# OBS-buttons-buttons.net
KiCad netlist of a schematic drawn in EAGLE
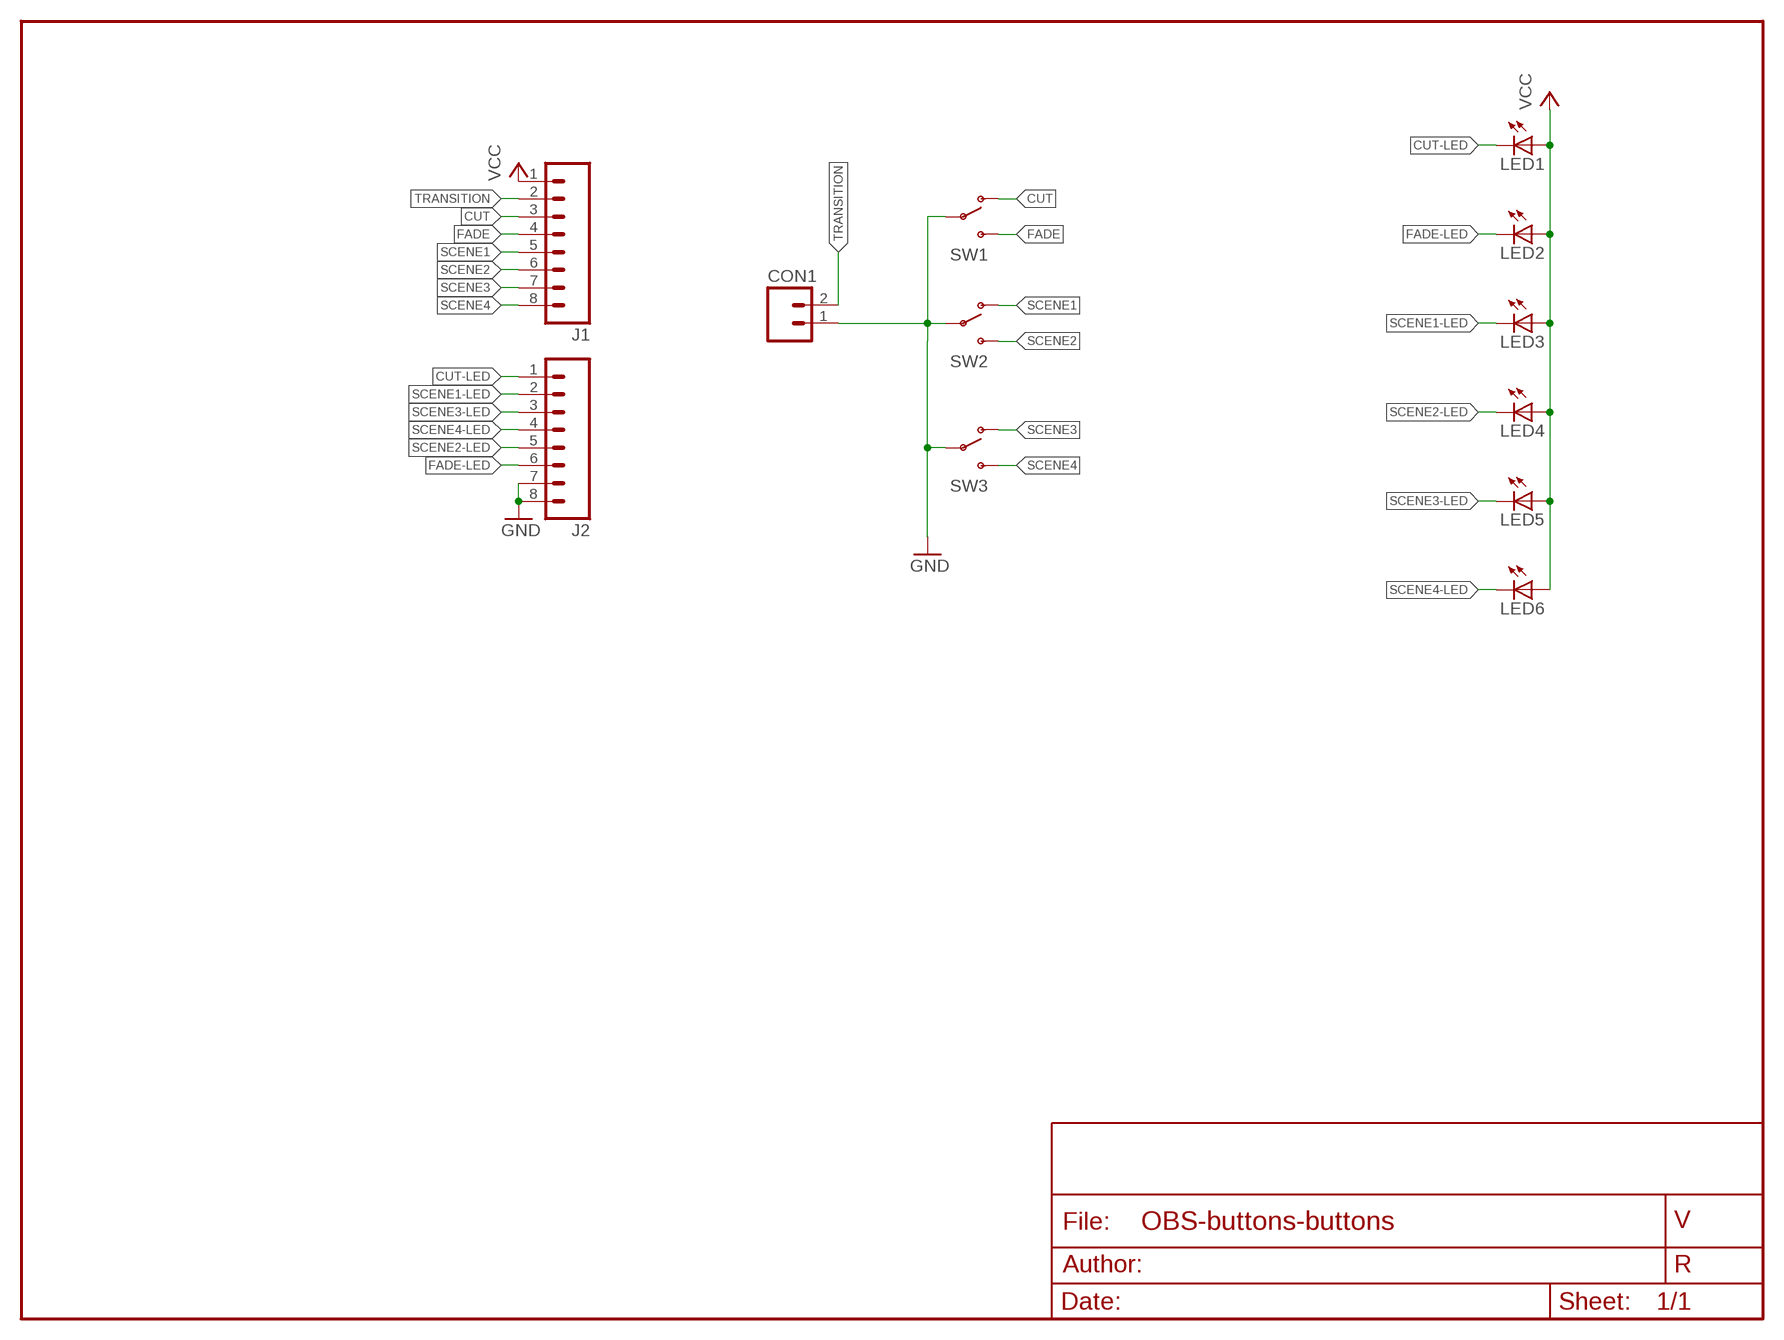
[diagram p0: schematic, sheet 1]

(export (version "E")
  (design (tool "Eeschema 10.0.6"))
  (components
    (comp (ref "CON1")
      (value "CONNECTOR-M02508-LOCK")
      (footprint "eagle-import:MSTB2")
      (libsource (lib "eagle-import") (part "CONNECTOR-M02508-LOCK"))
    )
    (comp (ref "J1")
      (value "CONNECTOR-M08LOCK")
      (footprint "eagle-import:1X08_LOCK")
      (libsource (lib "eagle-import") (part "CONNECTOR-M08LOCK"))
    )
    (comp (ref "J2")
      (value "CONNECTOR-M08LOCK")
      (footprint "eagle-import:1X08_LOCK")
      (libsource (lib "eagle-import") (part "CONNECTOR-M08LOCK"))
    )
    (comp (ref "LED1")
      (value "LEDLED5MM")
      (footprint "eagle-import:LED5MM")
      (libsource (lib "eagle-import") (part "LEDLED5MM"))
    )
    (comp (ref "LED2")
      (value "LEDLED5MM")
      (footprint "eagle-import:LED5MM")
      (libsource (lib "eagle-import") (part "LEDLED5MM"))
    )
    (comp (ref "LED3")
      (value "LEDLED5MM")
      (footprint "eagle-import:LED5MM")
      (libsource (lib "eagle-import") (part "LEDLED5MM"))
    )
    (comp (ref "LED4")
      (value "LEDLED5MM")
      (footprint "eagle-import:LED5MM")
      (libsource (lib "eagle-import") (part "LEDLED5MM"))
    )
    (comp (ref "LED5")
      (value "LEDLED5MM")
      (footprint "eagle-import:LED5MM")
      (libsource (lib "eagle-import") (part "LEDLED5MM"))
    )
    (comp (ref "LED6")
      (value "LEDLED5MM")
      (footprint "eagle-import:LED5MM")
      (libsource (lib "eagle-import") (part "LEDLED5MM"))
    )
    (comp (ref "SW1")
      (value "SWITCH-SPSTPTH-508")
      (footprint "eagle-import:SWITCH-SPDT-508")
      (libsource (lib "eagle-import") (part "SWITCH-SPSTPTH-508"))
    )
    (comp (ref "SW2")
      (value "SWITCH-SPSTPTH-508")
      (footprint "eagle-import:SWITCH-SPDT-508")
      (libsource (lib "eagle-import") (part "SWITCH-SPSTPTH-508"))
    )
    (comp (ref "SW3")
      (value "SWITCH-SPSTPTH-508")
      (footprint "eagle-import:SWITCH-SPDT-508")
      (libsource (lib "eagle-import") (part "SWITCH-SPSTPTH-508"))
    )
  )
  (nets
    (net (code "1") (name "CUT") (class "Default")
      (node (ref "J1") (pin "3") (pinfunction "3_3") (pintype "passive"))
      (node (ref "SW1") (pin "1") (pinfunction "O_1") (pintype "passive"))
    )
    (net (code "2") (name "CUT-LED") (class "Default")
      (node (ref "J2") (pin "1") (pinfunction "1_1") (pintype "passive"))
      (node (ref "LED1") (pin "K") (pinfunction "C_K") (pintype "passive"))
    )
    (net (code "3") (name "FADE") (class "Default")
      (node (ref "J1") (pin "4") (pinfunction "4_4") (pintype "passive"))
      (node (ref "SW1") (pin "3") (pinfunction "S_3") (pintype "passive"))
    )
    (net (code "4") (name "FADE-LED") (class "Default")
      (node (ref "J2") (pin "6") (pinfunction "6_6") (pintype "passive"))
      (node (ref "LED2") (pin "K") (pinfunction "C_K") (pintype "passive"))
    )
    (net (code "5") (name "GND") (class "Default")
      (node (ref "CON1") (pin "1") (pinfunction "A_1") (pintype "passive"))
      (node (ref "J2") (pin "7") (pinfunction "7_7") (pintype "passive"))
      (node (ref "J2") (pin "8") (pinfunction "8_8") (pintype "passive"))
      (node (ref "SW1") (pin "2") (pinfunction "P_2") (pintype "passive"))
      (node (ref "SW2") (pin "2") (pinfunction "P_2") (pintype "passive"))
      (node (ref "SW3") (pin "2") (pinfunction "P_2") (pintype "passive"))
    )
    (net (code "6") (name "SCENE1") (class "Default")
      (node (ref "J1") (pin "5") (pinfunction "5_5") (pintype "passive"))
      (node (ref "SW2") (pin "1") (pinfunction "O_1") (pintype "passive"))
    )
    (net (code "7") (name "SCENE1-LED") (class "Default")
      (node (ref "J2") (pin "2") (pinfunction "2_2") (pintype "passive"))
      (node (ref "LED3") (pin "K") (pinfunction "C_K") (pintype "passive"))
    )
    (net (code "8") (name "SCENE2") (class "Default")
      (node (ref "J1") (pin "6") (pinfunction "6_6") (pintype "passive"))
      (node (ref "SW2") (pin "3") (pinfunction "S_3") (pintype "passive"))
    )
    (net (code "9") (name "SCENE2-LED") (class "Default")
      (node (ref "J2") (pin "5") (pinfunction "5_5") (pintype "passive"))
      (node (ref "LED4") (pin "K") (pinfunction "C_K") (pintype "passive"))
    )
    (net (code "10") (name "SCENE3") (class "Default")
      (node (ref "J1") (pin "7") (pinfunction "7_7") (pintype "passive"))
      (node (ref "SW3") (pin "1") (pinfunction "O_1") (pintype "passive"))
    )
    (net (code "11") (name "SCENE3-LED") (class "Default")
      (node (ref "J2") (pin "3") (pinfunction "3_3") (pintype "passive"))
      (node (ref "LED5") (pin "K") (pinfunction "C_K") (pintype "passive"))
    )
    (net (code "12") (name "SCENE4") (class "Default")
      (node (ref "J1") (pin "8") (pinfunction "8_8") (pintype "passive"))
      (node (ref "SW3") (pin "3") (pinfunction "S_3") (pintype "passive"))
    )
    (net (code "13") (name "SCENE4-LED") (class "Default")
      (node (ref "J2") (pin "4") (pinfunction "4_4") (pintype "passive"))
      (node (ref "LED6") (pin "K") (pinfunction "C_K") (pintype "passive"))
    )
    (net (code "14") (name "TRANSITION") (class "Default")
      (node (ref "CON1") (pin "2") (pinfunction "B_2") (pintype "passive"))
      (node (ref "J1") (pin "2") (pinfunction "2_2") (pintype "passive"))
    )
    (net (code "15") (name "VCC") (class "Default")
      (node (ref "J1") (pin "1") (pinfunction "1_1") (pintype "passive"))
      (node (ref "LED1") (pin "A") (pinfunction "A_A") (pintype "passive"))
      (node (ref "LED2") (pin "A") (pinfunction "A_A") (pintype "passive"))
      (node (ref "LED3") (pin "A") (pinfunction "A_A") (pintype "passive"))
      (node (ref "LED4") (pin "A") (pinfunction "A_A") (pintype "passive"))
      (node (ref "LED5") (pin "A") (pinfunction "A_A") (pintype "passive"))
      (node (ref "LED6") (pin "A") (pinfunction "A_A") (pintype "passive"))
    )
  )
)
